# axiom_beta_plugin_module_1xPMOD_v0_1_8f7.net
KiCad netlist of a schematic drawn in EAGLE
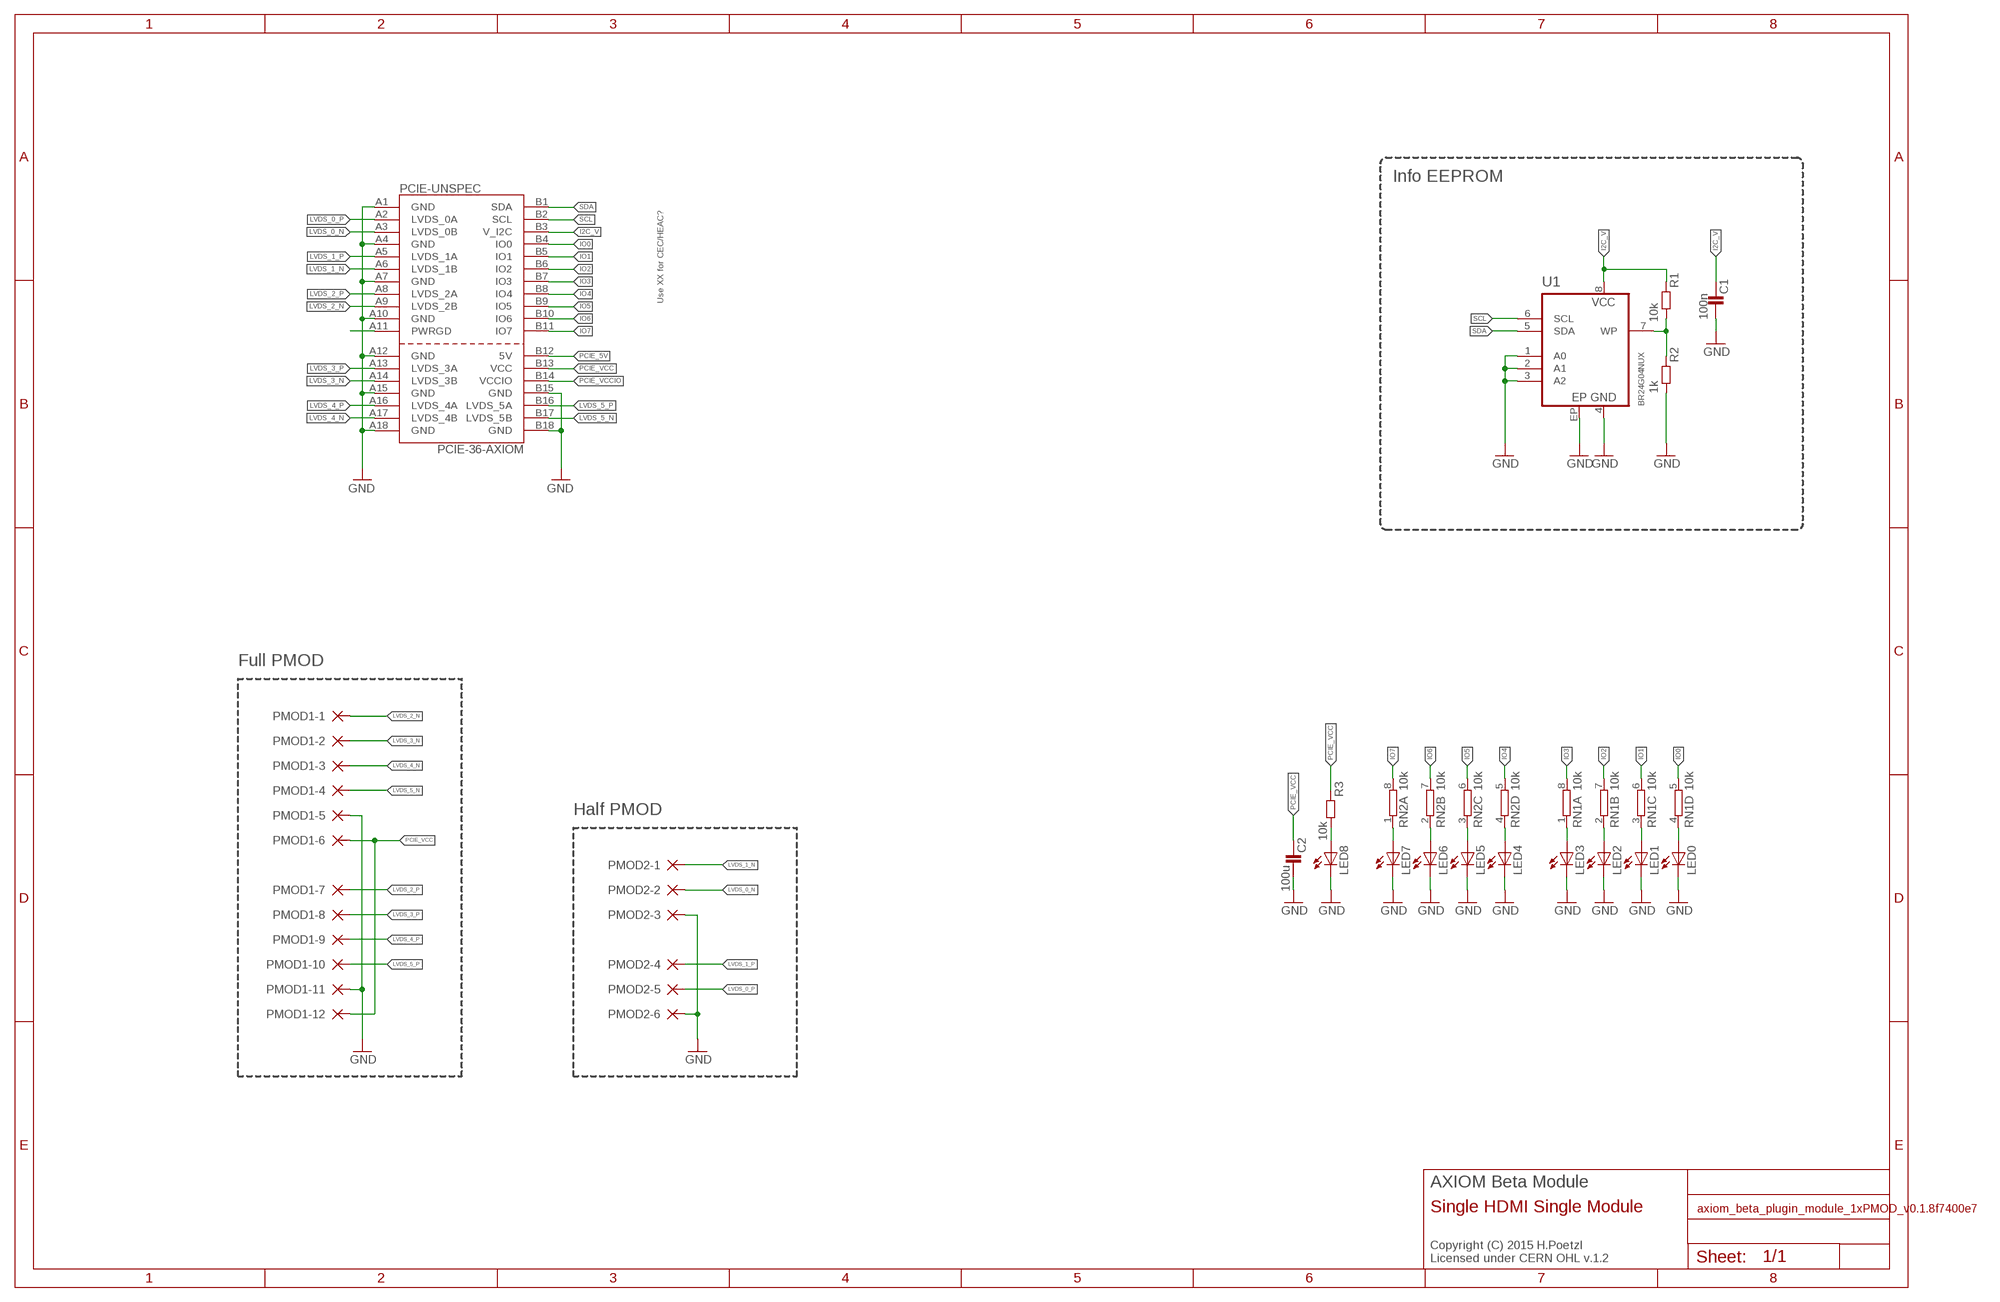
[diagram p0: schematic, sheet 1]

(export (version "E")
  (design (tool "Eeschema 10.0.6"))
  (components
    (comp (ref "C1")
      (value "100n")
      (footprint "eagle-import:0402-B")
      (libsource (lib "eagle-import") (part "C0402-B"))
    )
    (comp (ref "C2")
      (value "100u")
      (footprint "eagle-import:1206-A")
      (libsource (lib "eagle-import") (part "C1206-A"))
    )
    (comp (ref "LED0")
      (value "LEDCHIPLED_0603")
      (footprint "eagle-import:CHIPLED_0603")
      (libsource (lib "eagle-import") (part "LEDCHIPLED_0603"))
    )
    (comp (ref "LED1")
      (value "LEDCHIPLED_0603")
      (footprint "eagle-import:CHIPLED_0603")
      (libsource (lib "eagle-import") (part "LEDCHIPLED_0603"))
    )
    (comp (ref "LED2")
      (value "LEDCHIPLED_0603")
      (footprint "eagle-import:CHIPLED_0603")
      (libsource (lib "eagle-import") (part "LEDCHIPLED_0603"))
    )
    (comp (ref "LED3")
      (value "LEDCHIPLED_0603")
      (footprint "eagle-import:CHIPLED_0603")
      (libsource (lib "eagle-import") (part "LEDCHIPLED_0603"))
    )
    (comp (ref "LED4")
      (value "LEDCHIPLED_0603")
      (footprint "eagle-import:CHIPLED_0603")
      (libsource (lib "eagle-import") (part "LEDCHIPLED_0603"))
    )
    (comp (ref "LED5")
      (value "LEDCHIPLED_0603")
      (footprint "eagle-import:CHIPLED_0603")
      (libsource (lib "eagle-import") (part "LEDCHIPLED_0603"))
    )
    (comp (ref "LED6")
      (value "LEDCHIPLED_0603")
      (footprint "eagle-import:CHIPLED_0603")
      (libsource (lib "eagle-import") (part "LEDCHIPLED_0603"))
    )
    (comp (ref "LED7")
      (value "LEDCHIPLED_0603")
      (footprint "eagle-import:CHIPLED_0603")
      (libsource (lib "eagle-import") (part "LEDCHIPLED_0603"))
    )
    (comp (ref "LED8")
      (value "LEDCHIPLED_0603")
      (footprint "eagle-import:CHIPLED_0603")
      (libsource (lib "eagle-import") (part "LEDCHIPLED_0603"))
    )
    (comp (ref "PCIE-UNSPEC")
      (value "PCIE-36-AXIOM")
      (footprint "eagle-import:PCIE-36-AXIOM")
      (libsource (lib "eagle-import") (part "PCIE-36-AXIOM"))
    )
    (comp (ref "PMOD1-1")
      (value "SMD-PAD1.6X3.8MM-U")
      (footprint "eagle-import:1.6X3.8U-MM")
      (libsource (lib "eagle-import") (part "SMD-PAD1.6X3.8MM-U"))
    )
    (comp (ref "PMOD1-2")
      (value "SMD-PAD1.6X3.8MM-U")
      (footprint "eagle-import:1.6X3.8U-MM")
      (libsource (lib "eagle-import") (part "SMD-PAD1.6X3.8MM-U"))
    )
    (comp (ref "PMOD1-3")
      (value "SMD-PAD1.6X3.8MM-U")
      (footprint "eagle-import:1.6X3.8U-MM")
      (libsource (lib "eagle-import") (part "SMD-PAD1.6X3.8MM-U"))
    )
    (comp (ref "PMOD1-4")
      (value "SMD-PAD1.6X3.8MM-U")
      (footprint "eagle-import:1.6X3.8U-MM")
      (libsource (lib "eagle-import") (part "SMD-PAD1.6X3.8MM-U"))
    )
    (comp (ref "PMOD1-5")
      (value "SMD-PAD1.6X3.8MM-U")
      (footprint "eagle-import:1.6X3.8U-MM")
      (libsource (lib "eagle-import") (part "SMD-PAD1.6X3.8MM-U"))
    )
    (comp (ref "PMOD1-6")
      (value "SMD-PAD1.6X3.8MM-U")
      (footprint "eagle-import:1.6X3.8U-MM")
      (libsource (lib "eagle-import") (part "SMD-PAD1.6X3.8MM-U"))
    )
    (comp (ref "PMOD1-7")
      (value "SMD-PAD1.6X3.8MM-U")
      (footprint "eagle-import:1.6X3.8U-MM")
      (libsource (lib "eagle-import") (part "SMD-PAD1.6X3.8MM-U"))
    )
    (comp (ref "PMOD1-8")
      (value "SMD-PAD1.6X3.8MM-U")
      (footprint "eagle-import:1.6X3.8U-MM")
      (libsource (lib "eagle-import") (part "SMD-PAD1.6X3.8MM-U"))
    )
    (comp (ref "PMOD1-9")
      (value "SMD-PAD1.6X3.8MM-U")
      (footprint "eagle-import:1.6X3.8U-MM")
      (libsource (lib "eagle-import") (part "SMD-PAD1.6X3.8MM-U"))
    )
    (comp (ref "PMOD1-10")
      (value "SMD-PAD1.6X3.8MM-U")
      (footprint "eagle-import:1.6X3.8U-MM")
      (libsource (lib "eagle-import") (part "SMD-PAD1.6X3.8MM-U"))
    )
    (comp (ref "PMOD1-11")
      (value "SMD-PAD1.6X3.8MM-U")
      (footprint "eagle-import:1.6X3.8U-MM")
      (libsource (lib "eagle-import") (part "SMD-PAD1.6X3.8MM-U"))
    )
    (comp (ref "PMOD1-12")
      (value "SMD-PAD1.6X3.8MM-U")
      (footprint "eagle-import:1.6X3.8U-MM")
      (libsource (lib "eagle-import") (part "SMD-PAD1.6X3.8MM-U"))
    )
    (comp (ref "PMOD2-1")
      (value "SMD-PAD1.6X3.8MM-U")
      (footprint "eagle-import:1.6X3.8U-MM")
      (libsource (lib "eagle-import") (part "SMD-PAD1.6X3.8MM-U"))
    )
    (comp (ref "PMOD2-2")
      (value "SMD-PAD1.6X3.8MM-U")
      (footprint "eagle-import:1.6X3.8U-MM")
      (libsource (lib "eagle-import") (part "SMD-PAD1.6X3.8MM-U"))
    )
    (comp (ref "PMOD2-3")
      (value "SMD-PAD1.6X3.8MM-U")
      (footprint "eagle-import:1.6X3.8U-MM")
      (libsource (lib "eagle-import") (part "SMD-PAD1.6X3.8MM-U"))
    )
    (comp (ref "PMOD2-4")
      (value "SMD-PAD1.6X3.8MM-U")
      (footprint "eagle-import:1.6X3.8U-MM")
      (libsource (lib "eagle-import") (part "SMD-PAD1.6X3.8MM-U"))
    )
    (comp (ref "PMOD2-5")
      (value "SMD-PAD1.6X3.8MM-U")
      (footprint "eagle-import:1.6X3.8U-MM")
      (libsource (lib "eagle-import") (part "SMD-PAD1.6X3.8MM-U"))
    )
    (comp (ref "PMOD2-6")
      (value "SMD-PAD1.6X3.8MM-U")
      (footprint "eagle-import:1.6X3.8U-MM")
      (libsource (lib "eagle-import") (part "SMD-PAD1.6X3.8MM-U"))
    )
    (comp (ref "R1")
      (value "10k")
      (footprint "eagle-import:0402-B")
      (libsource (lib "eagle-import") (part "R0402-B"))
    )
    (comp (ref "R2")
      (value "1k")
      (footprint "eagle-import:0402-B")
      (libsource (lib "eagle-import") (part "R0402-B"))
    )
    (comp (ref "R3")
      (value "10k")
      (footprint "eagle-import:0402-B")
      (libsource (lib "eagle-import") (part "R0402-B"))
    )
    (comp (ref "RN1")
      (value "10k")
      (footprint "eagle-import:CAY16")
      (libsource (lib "eagle-import") (part "4R-NCAY16"))
    )
    (comp (ref "RN2")
      (value "10k")
      (footprint "eagle-import:CAY16")
      (libsource (lib "eagle-import") (part "4R-NCAY16"))
    )
    (comp (ref "U1")
      (value "BR24G04NUX")
      (footprint "eagle-import:DFN200X300X100-9N")
      (libsource (lib "eagle-import") (part "BR24G04NUX"))
    )
  )
  (nets
    (net (code "1") (name "GND") (class "Default")
      (node (ref "C1") (pin "2") (pinfunction "2_2") (pintype "passive"))
      (node (ref "C2") (pin "2") (pinfunction "2_2") (pintype "passive"))
      (node (ref "LED0") (pin "C") (pinfunction "C_C") (pintype "passive"))
      (node (ref "LED1") (pin "C") (pinfunction "C_C") (pintype "passive"))
      (node (ref "LED2") (pin "C") (pinfunction "C_C") (pintype "passive"))
      (node (ref "LED3") (pin "C") (pinfunction "C_C") (pintype "passive"))
      (node (ref "LED4") (pin "C") (pinfunction "C_C") (pintype "passive"))
      (node (ref "LED5") (pin "C") (pinfunction "C_C") (pintype "passive"))
      (node (ref "LED6") (pin "C") (pinfunction "C_C") (pintype "passive"))
      (node (ref "LED7") (pin "C") (pinfunction "C_C") (pintype "passive"))
      (node (ref "LED8") (pin "C") (pinfunction "C_C") (pintype "passive"))
      (node (ref "PCIE-UNSPEC") (pin "A1") (pinfunction "GND_A1") (pintype "passive"))
      (node (ref "PCIE-UNSPEC") (pin "A10") (pinfunction "GND_A10") (pintype "passive"))
      (node (ref "PCIE-UNSPEC") (pin "A12") (pinfunction "GND_A12") (pintype "passive"))
      (node (ref "PCIE-UNSPEC") (pin "A15") (pinfunction "GND_A15") (pintype "passive"))
      (node (ref "PCIE-UNSPEC") (pin "A18") (pinfunction "GND_A18") (pintype "passive"))
      (node (ref "PCIE-UNSPEC") (pin "A4") (pinfunction "GND_A4") (pintype "passive"))
      (node (ref "PCIE-UNSPEC") (pin "A7") (pinfunction "GND_A7") (pintype "passive"))
      (node (ref "PCIE-UNSPEC") (pin "B15") (pinfunction "GND_B15") (pintype "passive"))
      (node (ref "PCIE-UNSPEC") (pin "B18") (pinfunction "GND_B18") (pintype "passive"))
      (node (ref "PMOD1-11") (pin "1") (pinfunction "P_1") (pintype "passive"))
      (node (ref "PMOD1-5") (pin "1") (pinfunction "P_1") (pintype "passive"))
      (node (ref "PMOD2-3") (pin "1") (pinfunction "P_1") (pintype "passive"))
      (node (ref "PMOD2-6") (pin "1") (pinfunction "P_1") (pintype "passive"))
      (node (ref "R2") (pin "2") (pinfunction "2_2") (pintype "passive"))
      (node (ref "U1") (pin "1") (pinfunction "A0_1") (pintype "input"))
      (node (ref "U1") (pin "2") (pinfunction "A1_2") (pintype "input"))
      (node (ref "U1") (pin "3") (pinfunction "A2_3") (pintype "input"))
      (node (ref "U1") (pin "4") (pinfunction "GND_4") (pintype "passive"))
      (node (ref "U1") (pin "EP") (pinfunction "EP_EP") (pintype "passive"))
    )
    (net (code "2") (name "I2C_V") (class "Default")
      (node (ref "C1") (pin "1") (pinfunction "1_1") (pintype "passive"))
      (node (ref "PCIE-UNSPEC") (pin "B3") (pinfunction "V_I2C_B3") (pintype "passive"))
      (node (ref "R1") (pin "1") (pinfunction "1_1") (pintype "passive"))
      (node (ref "U1") (pin "8") (pinfunction "VCC_8") (pintype "power_in"))
    )
    (net (code "3") (name "IO0") (class "Default")
      (node (ref "PCIE-UNSPEC") (pin "B4") (pinfunction "IO0_B4") (pintype "passive"))
      (node (ref "RN1") (pin "5") (pinfunction "2_5") (pintype "passive"))
    )
    (net (code "4") (name "IO1") (class "Default")
      (node (ref "PCIE-UNSPEC") (pin "B5") (pinfunction "IO1_B5") (pintype "passive"))
      (node (ref "RN1") (pin "6") (pinfunction "2_6") (pintype "passive"))
    )
    (net (code "5") (name "IO2") (class "Default")
      (node (ref "PCIE-UNSPEC") (pin "B6") (pinfunction "IO2_B6") (pintype "passive"))
      (node (ref "RN1") (pin "7") (pinfunction "2_7") (pintype "passive"))
    )
    (net (code "6") (name "IO3") (class "Default")
      (node (ref "PCIE-UNSPEC") (pin "B7") (pinfunction "IO3_B7") (pintype "passive"))
      (node (ref "RN1") (pin "8") (pinfunction "2_8") (pintype "passive"))
    )
    (net (code "7") (name "IO4") (class "Default")
      (node (ref "PCIE-UNSPEC") (pin "B8") (pinfunction "IO4_B8") (pintype "passive"))
      (node (ref "RN2") (pin "5") (pinfunction "2_5") (pintype "passive"))
    )
    (net (code "8") (name "IO5") (class "Default")
      (node (ref "PCIE-UNSPEC") (pin "B9") (pinfunction "IO5_B9") (pintype "passive"))
      (node (ref "RN2") (pin "6") (pinfunction "2_6") (pintype "passive"))
    )
    (net (code "9") (name "IO6") (class "Default")
      (node (ref "PCIE-UNSPEC") (pin "B10") (pinfunction "IO6_B10") (pintype "passive"))
      (node (ref "RN2") (pin "7") (pinfunction "2_7") (pintype "passive"))
    )
    (net (code "10") (name "IO7") (class "Default")
      (node (ref "PCIE-UNSPEC") (pin "B11") (pinfunction "IO7_B11") (pintype "passive"))
      (node (ref "RN2") (pin "8") (pinfunction "2_8") (pintype "passive"))
    )
    (net (code "11") (name "LVDS_0_N") (class "Default")
      (node (ref "PCIE-UNSPEC") (pin "A3") (pinfunction "LVDS_0B_A3") (pintype "passive"))
      (node (ref "PMOD2-2") (pin "1") (pinfunction "P_1") (pintype "passive"))
    )
    (net (code "12") (name "LVDS_0_P") (class "Default")
      (node (ref "PCIE-UNSPEC") (pin "A2") (pinfunction "LVDS_0A_A2") (pintype "passive"))
      (node (ref "PMOD2-5") (pin "1") (pinfunction "P_1") (pintype "passive"))
    )
    (net (code "13") (name "LVDS_1_N") (class "Default")
      (node (ref "PCIE-UNSPEC") (pin "A6") (pinfunction "LVDS_1B_A6") (pintype "passive"))
      (node (ref "PMOD2-1") (pin "1") (pinfunction "P_1") (pintype "passive"))
    )
    (net (code "14") (name "LVDS_1_P") (class "Default")
      (node (ref "PCIE-UNSPEC") (pin "A5") (pinfunction "LVDS_1A_A5") (pintype "passive"))
      (node (ref "PMOD2-4") (pin "1") (pinfunction "P_1") (pintype "passive"))
    )
    (net (code "15") (name "LVDS_2_N") (class "Default")
      (node (ref "PCIE-UNSPEC") (pin "A9") (pinfunction "LVDS_2B_A9") (pintype "passive"))
      (node (ref "PMOD1-1") (pin "1") (pinfunction "P_1") (pintype "passive"))
    )
    (net (code "16") (name "LVDS_2_P") (class "Default")
      (node (ref "PCIE-UNSPEC") (pin "A8") (pinfunction "LVDS_2A_A8") (pintype "passive"))
      (node (ref "PMOD1-7") (pin "1") (pinfunction "P_1") (pintype "passive"))
    )
    (net (code "17") (name "LVDS_3_N") (class "Default")
      (node (ref "PCIE-UNSPEC") (pin "A14") (pinfunction "LVDS_3B_A14") (pintype "passive"))
      (node (ref "PMOD1-2") (pin "1") (pinfunction "P_1") (pintype "passive"))
    )
    (net (code "18") (name "LVDS_3_P") (class "Default")
      (node (ref "PCIE-UNSPEC") (pin "A13") (pinfunction "LVDS_3A_A13") (pintype "passive"))
      (node (ref "PMOD1-8") (pin "1") (pinfunction "P_1") (pintype "passive"))
    )
    (net (code "19") (name "LVDS_4_N") (class "Default")
      (node (ref "PCIE-UNSPEC") (pin "A17") (pinfunction "LVDS_4B_A17") (pintype "passive"))
      (node (ref "PMOD1-3") (pin "1") (pinfunction "P_1") (pintype "passive"))
    )
    (net (code "20") (name "LVDS_4_P") (class "Default")
      (node (ref "PCIE-UNSPEC") (pin "A16") (pinfunction "LVDS_4A_A16") (pintype "passive"))
      (node (ref "PMOD1-9") (pin "1") (pinfunction "P_1") (pintype "passive"))
    )
    (net (code "21") (name "LVDS_5_N") (class "Default")
      (node (ref "PCIE-UNSPEC") (pin "B17") (pinfunction "LVDS_5B_B17") (pintype "passive"))
      (node (ref "PMOD1-4") (pin "1") (pinfunction "P_1") (pintype "passive"))
    )
    (net (code "22") (name "LVDS_5_P") (class "Default")
      (node (ref "PCIE-UNSPEC") (pin "B16") (pinfunction "LVDS_5A_B16") (pintype "passive"))
      (node (ref "PMOD1-10") (pin "1") (pinfunction "P_1") (pintype "passive"))
    )
    (net (code "23") (name "Net-(LED3-PadA)") (class "Default")
      (node (ref "LED3") (pin "A") (pinfunction "A_A") (pintype "passive"))
      (node (ref "RN1") (pin "1") (pinfunction "1_1") (pintype "passive"))
    )
    (net (code "24") (name "Net-(LED7-PadA)") (class "Default")
      (node (ref "LED7") (pin "A") (pinfunction "A_A") (pintype "passive"))
      (node (ref "RN2") (pin "1") (pinfunction "1_1") (pintype "passive"))
    )
    (net (code "25") (name "Net-(LED8-PadA)") (class "Default")
      (node (ref "LED8") (pin "A") (pinfunction "A_A") (pintype "passive"))
      (node (ref "R3") (pin "2") (pinfunction "2_2") (pintype "passive"))
    )
    (net (code "26") (name "Net-(RN1B-1)") (class "Default")
      (node (ref "LED2") (pin "A") (pinfunction "A_A") (pintype "passive"))
      (node (ref "RN1") (pin "2") (pinfunction "1_2") (pintype "passive"))
    )
    (net (code "27") (name "Net-(RN1C-1)") (class "Default")
      (node (ref "LED1") (pin "A") (pinfunction "A_A") (pintype "passive"))
      (node (ref "RN1") (pin "3") (pinfunction "1_3") (pintype "passive"))
    )
    (net (code "28") (name "Net-(RN1D-1)") (class "Default")
      (node (ref "LED0") (pin "A") (pinfunction "A_A") (pintype "passive"))
      (node (ref "RN1") (pin "4") (pinfunction "1_4") (pintype "passive"))
    )
    (net (code "29") (name "Net-(RN2B-1)") (class "Default")
      (node (ref "LED6") (pin "A") (pinfunction "A_A") (pintype "passive"))
      (node (ref "RN2") (pin "2") (pinfunction "1_2") (pintype "passive"))
    )
    (net (code "30") (name "Net-(RN2C-1)") (class "Default")
      (node (ref "LED5") (pin "A") (pinfunction "A_A") (pintype "passive"))
      (node (ref "RN2") (pin "3") (pinfunction "1_3") (pintype "passive"))
    )
    (net (code "31") (name "Net-(RN2D-1)") (class "Default")
      (node (ref "LED4") (pin "A") (pinfunction "A_A") (pintype "passive"))
      (node (ref "RN2") (pin "4") (pinfunction "1_4") (pintype "passive"))
    )
    (net (code "32") (name "Net-(U1-WP)") (class "Default")
      (node (ref "R1") (pin "2") (pinfunction "2_2") (pintype "passive"))
      (node (ref "R2") (pin "1") (pinfunction "1_1") (pintype "passive"))
      (node (ref "U1") (pin "7") (pinfunction "WP_7") (pintype "input"))
    )
    (net (code "33") (name "PCIE_5V") (class "Default")
      (node (ref "PCIE-UNSPEC") (pin "B12") (pinfunction "5V_B12") (pintype "passive"))
    )
    (net (code "34") (name "PCIE_VCC") (class "Default")
      (node (ref "C2") (pin "1") (pinfunction "1_1") (pintype "passive"))
      (node (ref "PCIE-UNSPEC") (pin "B13") (pinfunction "VCC_B13") (pintype "passive"))
      (node (ref "PMOD1-12") (pin "1") (pinfunction "P_1") (pintype "passive"))
      (node (ref "PMOD1-6") (pin "1") (pinfunction "P_1") (pintype "passive"))
      (node (ref "R3") (pin "1") (pinfunction "1_1") (pintype "passive"))
    )
    (net (code "35") (name "PCIE_VCCIO") (class "Default")
      (node (ref "PCIE-UNSPEC") (pin "B14") (pinfunction "VCCIO_B14") (pintype "passive"))
    )
    (net (code "36") (name "SCL") (class "Default")
      (node (ref "PCIE-UNSPEC") (pin "B2") (pinfunction "SCL_B2") (pintype "passive"))
      (node (ref "U1") (pin "6") (pinfunction "SCL_6") (pintype "input"))
    )
    (net (code "37") (name "SDA") (class "Default")
      (node (ref "PCIE-UNSPEC") (pin "B1") (pinfunction "SDA_B1") (pintype "passive"))
      (node (ref "U1") (pin "5") (pinfunction "SDA_5") (pintype "bidirectional"))
    )
    (net (code "38") (name "unconnected-(PCIE-UNSPEC-PWRGD-PadA11)") (class "Default")
      (node (ref "PCIE-UNSPEC") (pin "A11") (pinfunction "PWRGD_A11") (pintype "passive"))
    )
  )
)
